# unipolar.net
KiCad netlist of a schematic drawn in EAGLE
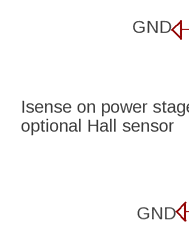
[diagram p0: schematic, sheet 1, part 1 of 2]
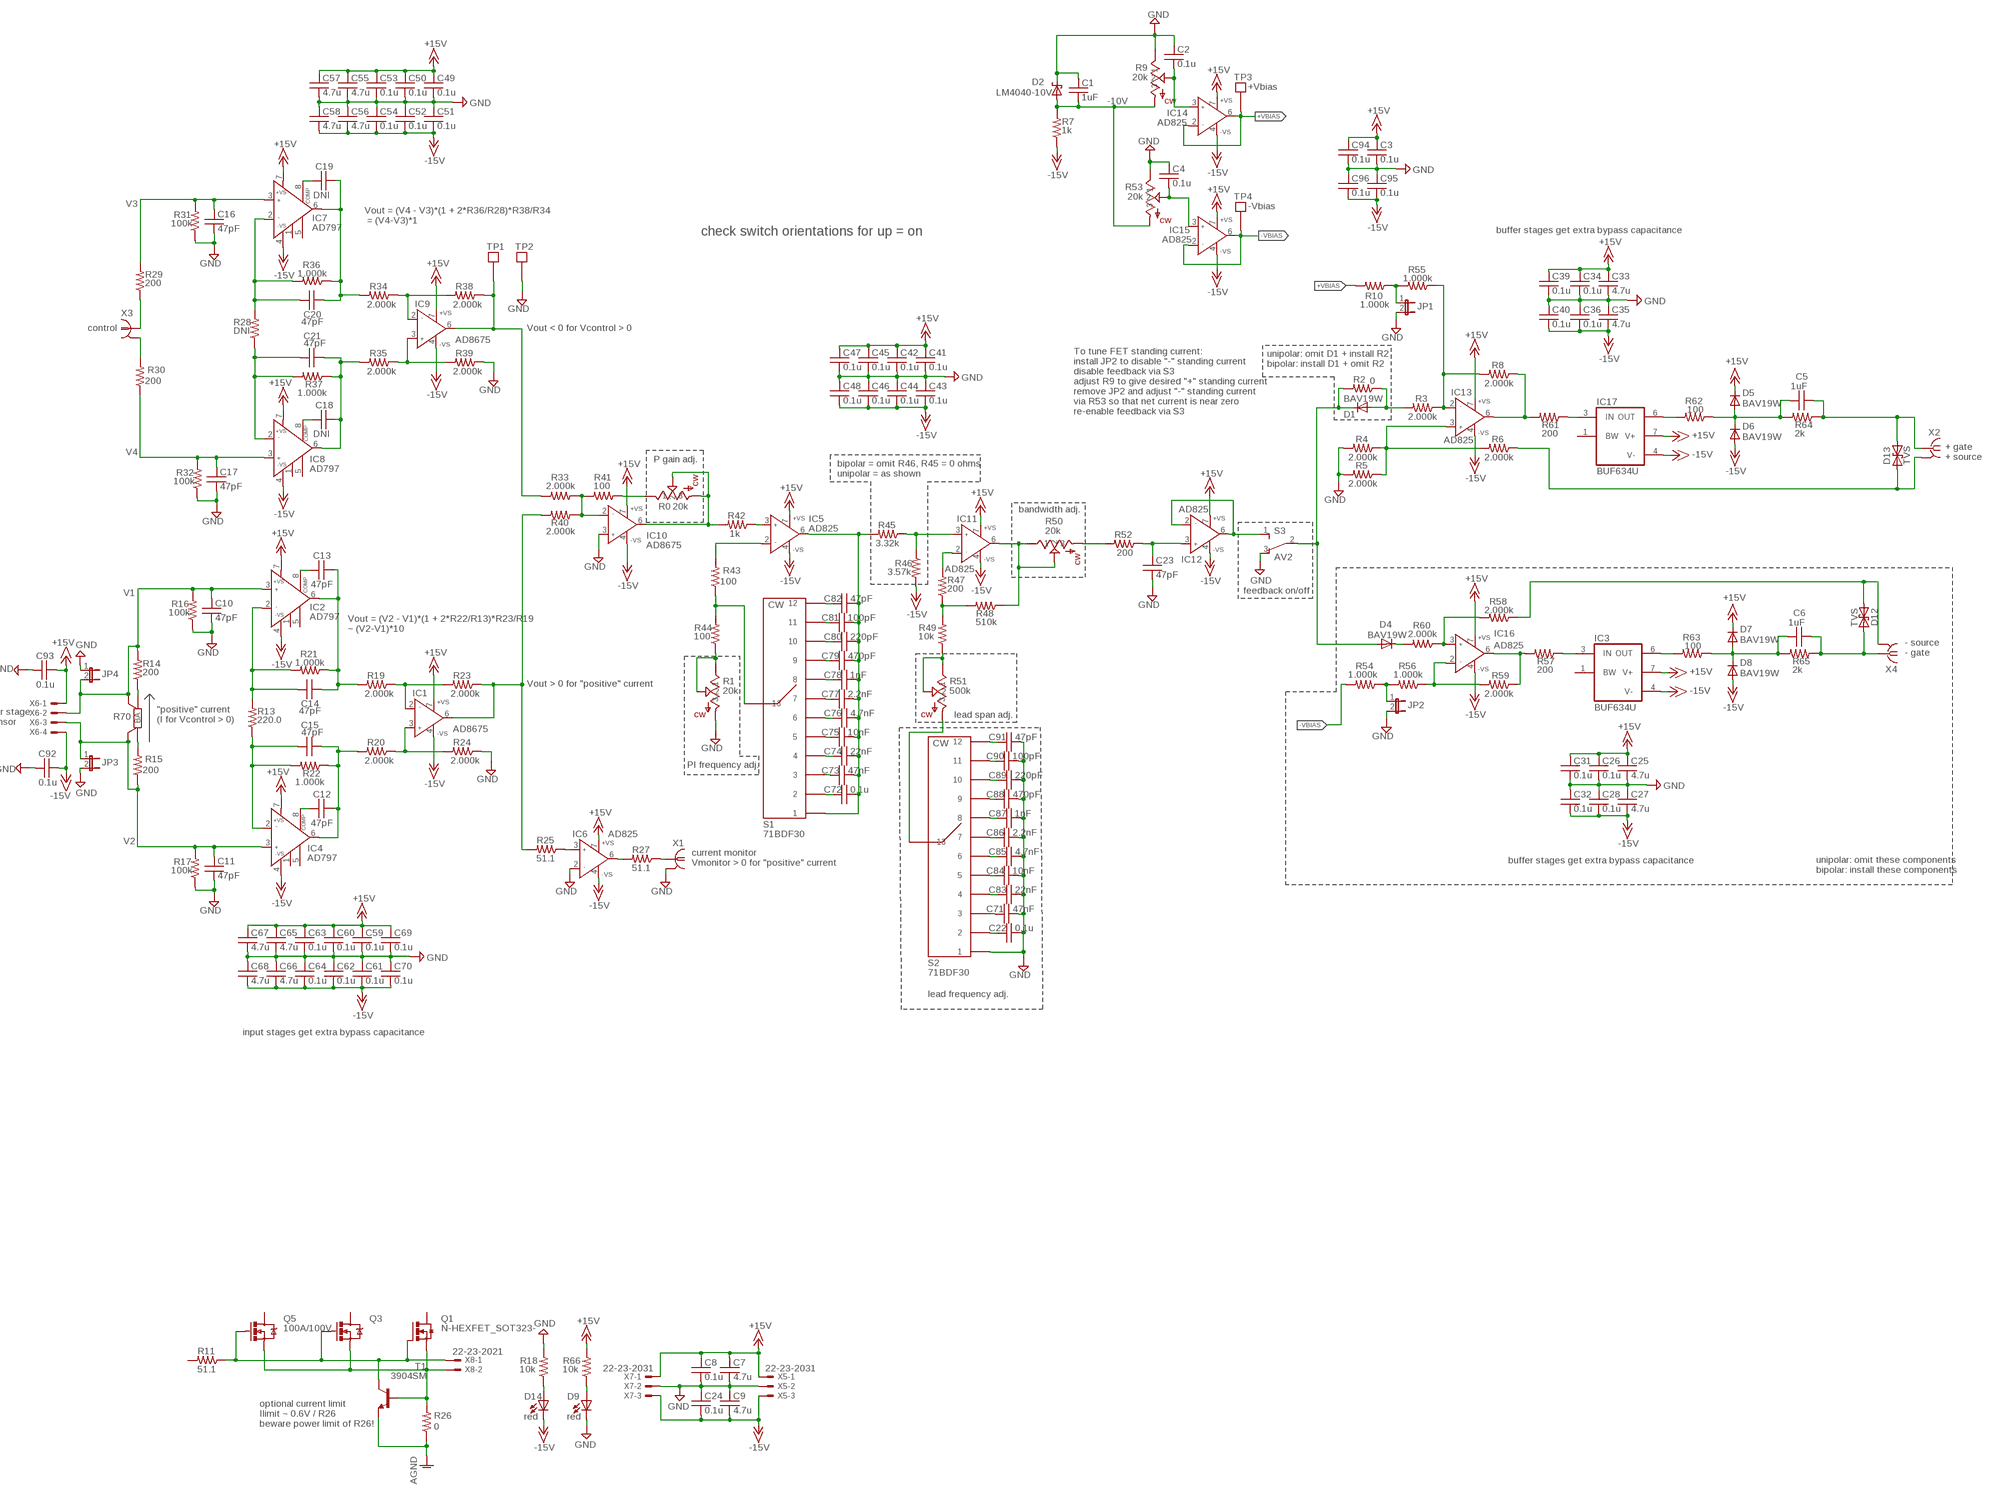
[diagram p1: schematic, sheet 1, part 2 of 2]

(export (version "E")
  (design (tool "Eeschema 10.0.6"))
  (components
    (comp (ref "C1")
      (value "1uF")
      (footprint "eagle-import:0603")
      (libsource (lib "eagle-import") (part "C0603"))
    )
    (comp (ref "C2")
      (value "0.1u")
      (footprint "eagle-import:0603")
      (libsource (lib "eagle-import") (part "C0603"))
    )
    (comp (ref "C3")
      (value "0.1u")
      (footprint "eagle-import:0603")
      (libsource (lib "eagle-import") (part "C0603"))
    )
    (comp (ref "C4")
      (value "0.1u")
      (footprint "eagle-import:0603")
      (libsource (lib "eagle-import") (part "C0603"))
    )
    (comp (ref "C5")
      (value "1uF")
      (footprint "eagle-import:0603")
      (libsource (lib "eagle-import") (part "C0603"))
    )
    (comp (ref "C6")
      (value "1uF")
      (footprint "eagle-import:0603")
      (libsource (lib "eagle-import") (part "C0603"))
    )
    (comp (ref "C7")
      (value "4.7u")
      (footprint "eagle-import:0603")
      (libsource (lib "eagle-import") (part "C0603"))
    )
    (comp (ref "C8")
      (value "0.1u")
      (footprint "eagle-import:0603")
      (libsource (lib "eagle-import") (part "C0603"))
    )
    (comp (ref "C9")
      (value "4.7u")
      (footprint "eagle-import:0603")
      (libsource (lib "eagle-import") (part "C0603"))
    )
    (comp (ref "C10")
      (value "47pF")
      (footprint "eagle-import:0603")
      (libsource (lib "eagle-import") (part "C0603"))
    )
    (comp (ref "C11")
      (value "47pF")
      (footprint "eagle-import:0603")
      (libsource (lib "eagle-import") (part "C0603"))
    )
    (comp (ref "C12")
      (value "47pF")
      (footprint "eagle-import:0603")
      (libsource (lib "eagle-import") (part "C0603"))
    )
    (comp (ref "C13")
      (value "47pF")
      (footprint "eagle-import:0603")
      (libsource (lib "eagle-import") (part "C0603"))
    )
    (comp (ref "C14")
      (value "47pF")
      (footprint "eagle-import:0603")
      (libsource (lib "eagle-import") (part "C0603"))
    )
    (comp (ref "C15")
      (value "47pF")
      (footprint "eagle-import:0603")
      (libsource (lib "eagle-import") (part "C0603"))
    )
    (comp (ref "C16")
      (value "47pF")
      (footprint "eagle-import:0603")
      (libsource (lib "eagle-import") (part "C0603"))
    )
    (comp (ref "C17")
      (value "47pF")
      (footprint "eagle-import:0603")
      (libsource (lib "eagle-import") (part "C0603"))
    )
    (comp (ref "C18")
      (value "DNI")
      (footprint "eagle-import:0603")
      (libsource (lib "eagle-import") (part "C0603"))
    )
    (comp (ref "C19")
      (value "DNI")
      (footprint "eagle-import:0603")
      (libsource (lib "eagle-import") (part "C0603"))
    )
    (comp (ref "C20")
      (value "47pF")
      (footprint "eagle-import:0603")
      (libsource (lib "eagle-import") (part "C0603"))
    )
    (comp (ref "C21")
      (value "47pF")
      (footprint "eagle-import:0603")
      (libsource (lib "eagle-import") (part "C0603"))
    )
    (comp (ref "C22")
      (value "0.1u")
      (footprint "eagle-import:0603")
      (libsource (lib "eagle-import") (part "C0603"))
    )
    (comp (ref "C23")
      (value "47pF")
      (footprint "eagle-import:0603")
      (libsource (lib "eagle-import") (part "C0603"))
    )
    (comp (ref "C24")
      (value "0.1u")
      (footprint "eagle-import:0603")
      (libsource (lib "eagle-import") (part "C0603"))
    )
    (comp (ref "C25")
      (value "4.7u")
      (footprint "eagle-import:0603")
      (libsource (lib "eagle-import") (part "C0603"))
    )
    (comp (ref "C26")
      (value "0.1u")
      (footprint "eagle-import:0603")
      (libsource (lib "eagle-import") (part "C0603"))
    )
    (comp (ref "C27")
      (value "4.7u")
      (footprint "eagle-import:0603")
      (libsource (lib "eagle-import") (part "C0603"))
    )
    (comp (ref "C28")
      (value "0.1u")
      (footprint "eagle-import:0603")
      (libsource (lib "eagle-import") (part "C0603"))
    )
    (comp (ref "C31")
      (value "0.1u")
      (footprint "eagle-import:0603")
      (libsource (lib "eagle-import") (part "C0603"))
    )
    (comp (ref "C32")
      (value "0.1u")
      (footprint "eagle-import:0603")
      (libsource (lib "eagle-import") (part "C0603"))
    )
    (comp (ref "C33")
      (value "4.7u")
      (footprint "eagle-import:0603")
      (libsource (lib "eagle-import") (part "C0603"))
    )
    (comp (ref "C34")
      (value "0.1u")
      (footprint "eagle-import:0603")
      (libsource (lib "eagle-import") (part "C0603"))
    )
    (comp (ref "C35")
      (value "4.7u")
      (footprint "eagle-import:0603")
      (libsource (lib "eagle-import") (part "C0603"))
    )
    (comp (ref "C36")
      (value "0.1u")
      (footprint "eagle-import:0603")
      (libsource (lib "eagle-import") (part "C0603"))
    )
    (comp (ref "C39")
      (value "0.1u")
      (footprint "eagle-import:0603")
      (libsource (lib "eagle-import") (part "C0603"))
    )
    (comp (ref "C40")
      (value "0.1u")
      (footprint "eagle-import:0603")
      (libsource (lib "eagle-import") (part "C0603"))
    )
    (comp (ref "C41")
      (value "0.1u")
      (footprint "eagle-import:0603")
      (libsource (lib "eagle-import") (part "C0603"))
    )
    (comp (ref "C42")
      (value "0.1u")
      (footprint "eagle-import:0603")
      (libsource (lib "eagle-import") (part "C0603"))
    )
    (comp (ref "C43")
      (value "0.1u")
      (footprint "eagle-import:0603")
      (libsource (lib "eagle-import") (part "C0603"))
    )
    (comp (ref "C44")
      (value "0.1u")
      (footprint "eagle-import:0603")
      (libsource (lib "eagle-import") (part "C0603"))
    )
    (comp (ref "C45")
      (value "0.1u")
      (footprint "eagle-import:0603")
      (libsource (lib "eagle-import") (part "C0603"))
    )
    (comp (ref "C46")
      (value "0.1u")
      (footprint "eagle-import:0603")
      (libsource (lib "eagle-import") (part "C0603"))
    )
    (comp (ref "C47")
      (value "0.1u")
      (footprint "eagle-import:0603")
      (libsource (lib "eagle-import") (part "C0603"))
    )
    (comp (ref "C48")
      (value "0.1u")
      (footprint "eagle-import:0603")
      (libsource (lib "eagle-import") (part "C0603"))
    )
    (comp (ref "C49")
      (value "0.1u")
      (footprint "eagle-import:0603")
      (libsource (lib "eagle-import") (part "C0603"))
    )
    (comp (ref "C50")
      (value "0.1u")
      (footprint "eagle-import:0603")
      (libsource (lib "eagle-import") (part "C0603"))
    )
    (comp (ref "C51")
      (value "0.1u")
      (footprint "eagle-import:0603")
      (libsource (lib "eagle-import") (part "C0603"))
    )
    (comp (ref "C52")
      (value "0.1u")
      (footprint "eagle-import:0603")
      (libsource (lib "eagle-import") (part "C0603"))
    )
    (comp (ref "C53")
      (value "0.1u")
      (footprint "eagle-import:0603")
      (libsource (lib "eagle-import") (part "C0603"))
    )
    (comp (ref "C54")
      (value "0.1u")
      (footprint "eagle-import:0603")
      (libsource (lib "eagle-import") (part "C0603"))
    )
    (comp (ref "C55")
      (value "4.7u")
      (footprint "eagle-import:0603")
      (libsource (lib "eagle-import") (part "C0603"))
    )
    (comp (ref "C56")
      (value "4.7u")
      (footprint "eagle-import:0603")
      (libsource (lib "eagle-import") (part "C0603"))
    )
    (comp (ref "C57")
      (value "4.7u")
      (footprint "eagle-import:0603")
      (libsource (lib "eagle-import") (part "C0603"))
    )
    (comp (ref "C58")
      (value "4.7u")
      (footprint "eagle-import:0603")
      (libsource (lib "eagle-import") (part "C0603"))
    )
    (comp (ref "C59")
      (value "0.1u")
      (footprint "eagle-import:0603")
      (libsource (lib "eagle-import") (part "C0603"))
    )
    (comp (ref "C60")
      (value "0.1u")
      (footprint "eagle-import:0603")
      (libsource (lib "eagle-import") (part "C0603"))
    )
    (comp (ref "C61")
      (value "0.1u")
      (footprint "eagle-import:0603")
      (libsource (lib "eagle-import") (part "C0603"))
    )
    (comp (ref "C62")
      (value "0.1u")
      (footprint "eagle-import:0603")
      (libsource (lib "eagle-import") (part "C0603"))
    )
    (comp (ref "C63")
      (value "0.1u")
      (footprint "eagle-import:0603")
      (libsource (lib "eagle-import") (part "C0603"))
    )
    (comp (ref "C64")
      (value "0.1u")
      (footprint "eagle-import:0603")
      (libsource (lib "eagle-import") (part "C0603"))
    )
    (comp (ref "C65")
      (value "4.7u")
      (footprint "eagle-import:0603")
      (libsource (lib "eagle-import") (part "C0603"))
    )
    (comp (ref "C66")
      (value "4.7u")
      (footprint "eagle-import:0603")
      (libsource (lib "eagle-import") (part "C0603"))
    )
    (comp (ref "C67")
      (value "4.7u")
      (footprint "eagle-import:0603")
      (libsource (lib "eagle-import") (part "C0603"))
    )
    (comp (ref "C68")
      (value "4.7u")
      (footprint "eagle-import:0603")
      (libsource (lib "eagle-import") (part "C0603"))
    )
    (comp (ref "C69")
      (value "0.1u")
      (footprint "eagle-import:0603")
      (libsource (lib "eagle-import") (part "C0603"))
    )
    (comp (ref "C70")
      (value "0.1u")
      (footprint "eagle-import:0603")
      (libsource (lib "eagle-import") (part "C0603"))
    )
    (comp (ref "C71")
      (value "47nF")
      (footprint "eagle-import:0603")
      (libsource (lib "eagle-import") (part "C0603"))
    )
    (comp (ref "C72")
      (value "0.1u")
      (footprint "eagle-import:0603")
      (libsource (lib "eagle-import") (part "C0603"))
    )
    (comp (ref "C73")
      (value "47nF")
      (footprint "eagle-import:0603")
      (libsource (lib "eagle-import") (part "C0603"))
    )
    (comp (ref "C74")
      (value "22nF")
      (footprint "eagle-import:0603")
      (libsource (lib "eagle-import") (part "C0603"))
    )
    (comp (ref "C75")
      (value "10nF")
      (footprint "eagle-import:0603")
      (libsource (lib "eagle-import") (part "C0603"))
    )
    (comp (ref "C76")
      (value "4.7nF")
      (footprint "eagle-import:0603")
      (libsource (lib "eagle-import") (part "C0603"))
    )
    (comp (ref "C77")
      (value "2.2nF")
      (footprint "eagle-import:0603")
      (libsource (lib "eagle-import") (part "C0603"))
    )
    (comp (ref "C78")
      (value "1nF")
      (footprint "eagle-import:0603")
      (libsource (lib "eagle-import") (part "C0603"))
    )
    (comp (ref "C79")
      (value "470pF")
      (footprint "eagle-import:0603")
      (libsource (lib "eagle-import") (part "C0603"))
    )
    (comp (ref "C80")
      (value "220pF")
      (footprint "eagle-import:0603")
      (libsource (lib "eagle-import") (part "C0603"))
    )
    (comp (ref "C81")
      (value "100pF")
      (footprint "eagle-import:0603")
      (libsource (lib "eagle-import") (part "C0603"))
    )
    (comp (ref "C82")
      (value "47pF")
      (footprint "eagle-import:0603")
      (libsource (lib "eagle-import") (part "C0603"))
    )
    (comp (ref "C83")
      (value "22nF")
      (footprint "eagle-import:0603")
      (libsource (lib "eagle-import") (part "C0603"))
    )
    (comp (ref "C84")
      (value "10nF")
      (footprint "eagle-import:0603")
      (libsource (lib "eagle-import") (part "C0603"))
    )
    (comp (ref "C85")
      (value "4.7nF")
      (footprint "eagle-import:0603")
      (libsource (lib "eagle-import") (part "C0603"))
    )
    (comp (ref "C86")
      (value "2.2nF")
      (footprint "eagle-import:0603")
      (libsource (lib "eagle-import") (part "C0603"))
    )
    (comp (ref "C87")
      (value "1nF")
      (footprint "eagle-import:0603")
      (libsource (lib "eagle-import") (part "C0603"))
    )
    (comp (ref "C88")
      (value "470pF")
      (footprint "eagle-import:0603")
      (libsource (lib "eagle-import") (part "C0603"))
    )
    (comp (ref "C89")
      (value "220pF")
      (footprint "eagle-import:0603")
      (libsource (lib "eagle-import") (part "C0603"))
    )
    (comp (ref "C90")
      (value "100pF")
      (footprint "eagle-import:0603")
      (libsource (lib "eagle-import") (part "C0603"))
    )
    (comp (ref "C91")
      (value "47pF")
      (footprint "eagle-import:0603")
      (libsource (lib "eagle-import") (part "C0603"))
    )
    (comp (ref "C92")
      (value "0.1u")
      (footprint "eagle-import:0603")
      (libsource (lib "eagle-import") (part "C0603"))
    )
    (comp (ref "C93")
      (value "0.1u")
      (footprint "eagle-import:0603")
      (libsource (lib "eagle-import") (part "C0603"))
    )
    (comp (ref "C94")
      (value "0.1u")
      (footprint "eagle-import:0603")
      (libsource (lib "eagle-import") (part "C0603"))
    )
    (comp (ref "C95")
      (value "0.1u")
      (footprint "eagle-import:0603")
      (libsource (lib "eagle-import") (part "C0603"))
    )
    (comp (ref "C96")
      (value "0.1u")
      (footprint "eagle-import:0603")
      (libsource (lib "eagle-import") (part "C0603"))
    )
    (comp (ref "D1")
      (value "BAV19W")
      (footprint "eagle-import:SOD123")
      (libsource (lib "eagle-import") (part "DIODE-SOD123"))
    )
    (comp (ref "D2")
      (value "LM4040-10V")
      (footprint "eagle-import:SOT23")
      (libsource (lib "eagle-import") (part "LM4040"))
    )
    (comp (ref "D4")
      (value "BAV19W")
      (footprint "eagle-import:SOD123")
      (libsource (lib "eagle-import") (part "DIODE-SOD123"))
    )
    (comp (ref "D5")
      (value "BAV19W")
      (footprint "eagle-import:SOD123")
      (libsource (lib "eagle-import") (part "DIODE-SOD123"))
    )
    (comp (ref "D6")
      (value "BAV19W")
      (footprint "eagle-import:SOD123")
      (libsource (lib "eagle-import") (part "DIODE-SOD123"))
    )
    (comp (ref "D7")
      (value "BAV19W")
      (footprint "eagle-import:SOD123")
      (libsource (lib "eagle-import") (part "DIODE-SOD123"))
    )
    (comp (ref "D8")
      (value "BAV19W")
      (footprint "eagle-import:SOD123")
      (libsource (lib "eagle-import") (part "DIODE-SOD123"))
    )
    (comp (ref "D9")
      (value "red")
      (footprint "eagle-import:LED0603")
      (libsource (lib "eagle-import") (part "LED0603"))
    )
    (comp (ref "D12")
      (value "TVS")
      (footprint "eagle-import:SMA-DIODE")
      (libsource (lib "eagle-import") (part "TVS"))
    )
    (comp (ref "D13")
      (value "TVS")
      (footprint "eagle-import:SMA-DIODE")
      (libsource (lib "eagle-import") (part "TVS"))
    )
    (comp (ref "D14")
      (value "red")
      (footprint "eagle-import:LED0603")
      (libsource (lib "eagle-import") (part "LED0603"))
    )
    (comp (ref "IC1")
      (value "AD8675")
      (footprint "eagle-import:SO8")
      (fields (field (name "MF") "ALTERA CORPORATION") (field (name "MPN") "AD825ARZ"))
      (libsource (lib "eagle-import") (part "AD825_BR"))
    )
    (comp (ref "IC2")
      (value "AD797")
      (footprint "eagle-import:SO8")
      (fields (field (name "MF") "ALTERA CORPORATION") (field (name "MPN") "AD797ARZ"))
      (libsource (lib "eagle-import") (part "AD797_AR"))
    )
    (comp (ref "IC3")
      (value "BUF634U")
      (footprint "eagle-import:SO08")
      (fields (field (name "MF") "TEXAS INSTRUMENTS"))
      (libsource (lib "eagle-import") (part "BUF634U"))
    )
    (comp (ref "IC4")
      (value "AD797")
      (footprint "eagle-import:SO8")
      (fields (field (name "MF") "ALTERA CORPORATION") (field (name "MPN") "AD797ARZ"))
      (libsource (lib "eagle-import") (part "AD797_BR"))
    )
    (comp (ref "IC5")
      (value "AD825")
      (footprint "eagle-import:SO08")
      (libsource (lib "eagle-import") (part "AD825_A"))
    )
    (comp (ref "IC6")
      (value "AD825")
      (footprint "eagle-import:SO08")
      (libsource (lib "eagle-import") (part "AD825_A"))
    )
    (comp (ref "IC7")
      (value "AD797")
      (footprint "eagle-import:SO8")
      (fields (field (name "MF") "ALTERA CORPORATION") (field (name "MPN") "AD797ARZ"))
      (libsource (lib "eagle-import") (part "AD797_AR"))
    )
    (comp (ref "IC8")
      (value "AD797")
      (footprint "eagle-import:SO8")
      (fields (field (name "MF") "ALTERA CORPORATION") (field (name "MPN") "AD797ARZ"))
      (libsource (lib "eagle-import") (part "AD797_BR"))
    )
    (comp (ref "IC9")
      (value "AD8675")
      (footprint "eagle-import:SO8")
      (fields (field (name "MF") "ALTERA CORPORATION") (field (name "MPN") "AD825ARZ"))
      (libsource (lib "eagle-import") (part "AD825_BR"))
    )
    (comp (ref "IC10")
      (value "AD8675")
      (footprint "eagle-import:SO8")
      (fields (field (name "MF") "ALTERA CORPORATION") (field (name "MPN") "AD825ARZ"))
      (libsource (lib "eagle-import") (part "AD825_BR"))
    )
    (comp (ref "IC11")
      (value "AD825")
      (footprint "eagle-import:SO08")
      (libsource (lib "eagle-import") (part "AD825_A"))
    )
    (comp (ref "IC12")
      (value "AD825")
      (footprint "eagle-import:SO8")
      (fields (field (name "MF") "ALTERA CORPORATION") (field (name "MPN") "AD825ARZ"))
      (libsource (lib "eagle-import") (part "AD825_BR"))
    )
    (comp (ref "IC13")
      (value "AD825")
      (footprint "eagle-import:SO8")
      (fields (field (name "MF") "ALTERA CORPORATION") (field (name "MPN") "AD825ARZ"))
      (libsource (lib "eagle-import") (part "AD825_BR"))
    )
    (comp (ref "IC14")
      (value "AD825")
      (footprint "eagle-import:SO08")
      (libsource (lib "eagle-import") (part "AD825_A"))
    )
    (comp (ref "IC15")
      (value "AD825")
      (footprint "eagle-import:SO08")
      (libsource (lib "eagle-import") (part "AD825_A"))
    )
    (comp (ref "IC16")
      (value "AD825")
      (footprint "eagle-import:SO08")
      (libsource (lib "eagle-import") (part "AD825_A"))
    )
    (comp (ref "IC17")
      (value "BUF634U")
      (footprint "eagle-import:SO08")
      (fields (field (name "MF") "TEXAS INSTRUMENTS"))
      (libsource (lib "eagle-import") (part "BUF634U"))
    )
    (comp (ref "JP1")
      (value "JP1E")
      (footprint "eagle-import:JP1")
      (libsource (lib "eagle-import") (part "JP1E"))
    )
    (comp (ref "JP2")
      (value "JP1E")
      (footprint "eagle-import:JP1")
      (libsource (lib "eagle-import") (part "JP1E"))
    )
    (comp (ref "JP3")
      (value "JP1E")
      (footprint "eagle-import:JP1")
      (libsource (lib "eagle-import") (part "JP1E"))
    )
    (comp (ref "JP4")
      (value "JP1E")
      (footprint "eagle-import:JP1")
      (libsource (lib "eagle-import") (part "JP1E"))
    )
    (comp (ref "Q1")
      (value "N-HEXFET_SOT323-")
      (footprint "eagle-import:SOT223")
      (libsource (lib "eagle-import") (part "N-HEXFET_?-SOT323"))
    )
    (comp (ref "Q3")
      (value "MOSFET-NCHANNELFDD8780")
      (footprint "eagle-import:DPAK")
      (libsource (lib "eagle-import") (part "MOSFET-NCHANNELFDD8780"))
    )
    (comp (ref "Q5")
      (value "100A/100V")
      (footprint "eagle-import:TO-263_D2PAK")
      (libsource (lib "eagle-import") (part "MOSFET-NCHANNELPSMN7R0"))
    )
    (comp (ref "R0")
      (value "20k")
      (footprint "eagle-import:3590")
      (libsource (lib "eagle-import") (part "POT"))
    )
    (comp (ref "R1")
      (value "20k")
      (footprint "eagle-import:SP19L")
      (libsource (lib "eagle-import") (part "TRIM_US-B90P"))
    )
    (comp (ref "R2")
      (value "0")
      (footprint "eagle-import:0603")
      (libsource (lib "eagle-import") (part "R0603"))
    )
    (comp (ref "R3")
      (value "2.000k")
      (footprint "eagle-import:0603")
      (libsource (lib "eagle-import") (part "R0603"))
    )
    (comp (ref "R4")
      (value "2.000k")
      (footprint "eagle-import:0603")
      (libsource (lib "eagle-import") (part "R0603"))
    )
    (comp (ref "R5")
      (value "2.000k")
      (footprint "eagle-import:0603")
      (libsource (lib "eagle-import") (part "R0603"))
    )
    (comp (ref "R6")
      (value "2.000k")
      (footprint "eagle-import:0603")
      (libsource (lib "eagle-import") (part "R0603"))
    )
    (comp (ref "R7")
      (value "1k")
      (footprint "eagle-import:0603")
      (libsource (lib "eagle-import") (part "R0603"))
    )
    (comp (ref "R8")
      (value "2.000k")
      (footprint "eagle-import:0603")
      (libsource (lib "eagle-import") (part "R0603"))
    )
    (comp (ref "R9")
      (value "20k")
      (footprint "eagle-import:SP19L")
      (libsource (lib "eagle-import") (part "TRIM_US-B90P"))
    )
    (comp (ref "R10")
      (value "1.000k")
      (footprint "eagle-import:0603")
      (libsource (lib "eagle-import") (part "R0603"))
    )
    (comp (ref "R11")
      (value "51.1")
      (footprint "eagle-import:0603")
      (libsource (lib "eagle-import") (part "R0603"))
    )
    (comp (ref "R13")
      (value "220.0")
      (footprint "eagle-import:0603")
      (libsource (lib "eagle-import") (part "R0603"))
    )
    (comp (ref "R14")
      (value "200")
      (footprint "eagle-import:0603")
      (libsource (lib "eagle-import") (part "R0603"))
    )
    (comp (ref "R15")
      (value "200")
      (footprint "eagle-import:0603")
      (libsource (lib "eagle-import") (part "R0603"))
    )
    (comp (ref "R16")
      (value "100k")
      (footprint "eagle-import:0603")
      (libsource (lib "eagle-import") (part "R0603"))
    )
    (comp (ref "R17")
      (value "100k")
      (footprint "eagle-import:0603")
      (libsource (lib "eagle-import") (part "R0603"))
    )
    (comp (ref "R18")
      (value "10k")
      (footprint "eagle-import:0603")
      (libsource (lib "eagle-import") (part "R0603"))
    )
    (comp (ref "R19")
      (value "2.000k")
      (footprint "eagle-import:0603")
      (libsource (lib "eagle-import") (part "R0603"))
    )
    (comp (ref "R20")
      (value "2.000k")
      (footprint "eagle-import:0603")
      (libsource (lib "eagle-import") (part "R0603"))
    )
    (comp (ref "R21")
      (value "1.000k")
      (footprint "eagle-import:0603")
      (libsource (lib "eagle-import") (part "R0603"))
    )
    (comp (ref "R22")
      (value "1.000k")
      (footprint "eagle-import:0603")
      (libsource (lib "eagle-import") (part "R0603"))
    )
    (comp (ref "R23")
      (value "2.000k")
      (footprint "eagle-import:0603")
      (libsource (lib "eagle-import") (part "R0603"))
    )
    (comp (ref "R24")
      (value "2.000k")
      (footprint "eagle-import:0603")
      (libsource (lib "eagle-import") (part "R0603"))
    )
    (comp (ref "R25")
      (value "51.1")
      (footprint "eagle-import:0603")
      (libsource (lib "eagle-import") (part "R0603"))
    )
    (comp (ref "R26")
      (value "0")
      (footprint "eagle-import:2512")
      (libsource (lib "eagle-import") (part "RESISTOR2512"))
    )
    (comp (ref "R27")
      (value "51.1")
      (footprint "eagle-import:0603")
      (libsource (lib "eagle-import") (part "R0603"))
    )
    (comp (ref "R28")
      (value "DNI")
      (footprint "eagle-import:0603")
      (libsource (lib "eagle-import") (part "R0603"))
    )
    (comp (ref "R29")
      (value "200")
      (footprint "eagle-import:0603")
      (libsource (lib "eagle-import") (part "R0603"))
    )
    (comp (ref "R30")
      (value "200")
      (footprint "eagle-import:0603")
      (libsource (lib "eagle-import") (part "R0603"))
    )
    (comp (ref "R31")
      (value "100k")
      (footprint "eagle-import:0603")
      (libsource (lib "eagle-import") (part "R0603"))
    )
    (comp (ref "R32")
      (value "100k")
      (footprint "eagle-import:0603")
      (libsource (lib "eagle-import") (part "R0603"))
    )
    (comp (ref "R33")
      (value "2.000k")
      (footprint "eagle-import:0603")
      (libsource (lib "eagle-import") (part "R0603"))
    )
    (comp (ref "R34")
      (value "2.000k")
      (footprint "eagle-import:0603")
      (libsource (lib "eagle-import") (part "R0603"))
    )
    (comp (ref "R35")
      (value "2.000k")
      (footprint "eagle-import:0603")
      (libsource (lib "eagle-import") (part "R0603"))
    )
    (comp (ref "R36")
      (value "1.000k")
      (footprint "eagle-import:0603")
      (libsource (lib "eagle-import") (part "R0603"))
    )
    (comp (ref "R37")
      (value "1.000k")
      (footprint "eagle-import:0603")
      (libsource (lib "eagle-import") (part "R0603"))
    )
    (comp (ref "R38")
      (value "2.000k")
      (footprint "eagle-import:0603")
      (libsource (lib "eagle-import") (part "R0603"))
    )
    (comp (ref "R39")
      (value "2.000k")
      (footprint "eagle-import:0603")
      (libsource (lib "eagle-import") (part "R0603"))
    )
    (comp (ref "R40")
      (value "2.000k")
      (footprint "eagle-import:0603")
      (libsource (lib "eagle-import") (part "R0603"))
    )
    (comp (ref "R41")
      (value "100")
      (footprint "eagle-import:0603")
      (libsource (lib "eagle-import") (part "R0603"))
    )
    (comp (ref "R42")
      (value "1k")
      (footprint "eagle-import:0603")
      (libsource (lib "eagle-import") (part "R0603"))
    )
    (comp (ref "R43")
      (value "100")
      (footprint "eagle-import:0603")
      (libsource (lib "eagle-import") (part "R0603"))
    )
    (comp (ref "R44")
      (value "100")
      (footprint "eagle-import:0603")
      (libsource (lib "eagle-import") (part "R0603"))
    )
    (comp (ref "R45")
      (value "3.32k")
      (footprint "eagle-import:0603")
      (libsource (lib "eagle-import") (part "R0603"))
    )
    (comp (ref "R46")
      (value "3.57k")
      (footprint "eagle-import:0603")
      (libsource (lib "eagle-import") (part "R0603"))
    )
    (comp (ref "R47")
      (value "200")
      (footprint "eagle-import:0603")
      (libsource (lib "eagle-import") (part "R0603"))
    )
    (comp (ref "R48")
      (value "510k")
      (footprint "eagle-import:0603")
      (libsource (lib "eagle-import") (part "R0603"))
    )
    (comp (ref "R49")
      (value "10k")
      (footprint "eagle-import:0603")
      (libsource (lib "eagle-import") (part "R0603"))
    )
    (comp (ref "R50")
      (value "20k")
      (footprint "eagle-import:SP19L")
      (libsource (lib "eagle-import") (part "TRIM_US-B90P"))
    )
    (comp (ref "R51")
      (value "500k")
      (footprint "eagle-import:SP19L")
      (libsource (lib "eagle-import") (part "TRIM_US-B90P"))
    )
    (comp (ref "R52")
      (value "200")
      (footprint "eagle-import:0603")
      (libsource (lib "eagle-import") (part "R0603"))
    )
    (comp (ref "R53")
      (value "20k")
      (footprint "eagle-import:SP19L")
      (libsource (lib "eagle-import") (part "TRIM_US-B90P"))
    )
    (comp (ref "R54")
      (value "1.000k")
      (footprint "eagle-import:0603")
      (libsource (lib "eagle-import") (part "R0603"))
    )
    (comp (ref "R55")
      (value "1.000k")
      (footprint "eagle-import:0603")
      (libsource (lib "eagle-import") (part "R0603"))
    )
    (comp (ref "R56")
      (value "1.000k")
      (footprint "eagle-import:0603")
      (libsource (lib "eagle-import") (part "R0603"))
    )
    (comp (ref "R57")
      (value "200")
      (footprint "eagle-import:0603")
      (libsource (lib "eagle-import") (part "R0603"))
    )
    (comp (ref "R58")
      (value "2.000k")
      (footprint "eagle-import:0603")
      (libsource (lib "eagle-import") (part "R0603"))
    )
    (comp (ref "R59")
      (value "2.000k")
      (footprint "eagle-import:0603")
      (libsource (lib "eagle-import") (part "R0603"))
    )
    (comp (ref "R60")
      (value "2.000k")
      (footprint "eagle-import:0603")
      (libsource (lib "eagle-import") (part "R0603"))
    )
    (comp (ref "R61")
      (value "200")
      (footprint "eagle-import:0603")
      (libsource (lib "eagle-import") (part "R0603"))
    )
    (comp (ref "R62")
      (value "100")
      (footprint "eagle-import:0603")
      (libsource (lib "eagle-import") (part "R0603"))
    )
    (comp (ref "R63")
      (value "100")
      (footprint "eagle-import:0603")
      (libsource (lib "eagle-import") (part "R0603"))
    )
    (comp (ref "R64")
      (value "2k")
      (footprint "eagle-import:0603")
      (libsource (lib "eagle-import") (part "R0603"))
    )
    (comp (ref "R65")
      (value "2k")
      (footprint "eagle-import:0603")
      (libsource (lib "eagle-import") (part "R0603"))
    )
    (comp (ref "R66")
      (value "10k")
      (footprint "eagle-import:0603")
      (libsource (lib "eagle-import") (part "R0603"))
    )
    (comp (ref "R70")
      (value "RSENSE")
      (footprint "eagle-import:22-23-2041")
      (libsource (lib "eagle-import") (part "RSENSE"))
    )
    (comp (ref "S1")
      (value "71BDF30")
      (footprint "eagle-import:71BDF")
      (libsource (lib "eagle-import") (part "71BDF30"))
    )
    (comp (ref "S2")
      (value "71BDF30")
      (footprint "eagle-import:71BDF")
      (libsource (lib "eagle-import") (part "71BDF30"))
    )
    (comp (ref "S3")
      (value "AV2")
      (footprint "eagle-import:SPDT-AV2")
      (libsource (lib "eagle-import") (part "SPDT"))
    )
    (comp (ref "T1")
      (value "3904SM")
      (footprint "eagle-import:SOT23")
      (libsource (lib "eagle-import") (part "3904SM"))
    )
    (comp (ref "TP1")
      (value "TESTPOINT")
      (footprint "eagle-import:TESTPOINT")
      (libsource (lib "eagle-import") (part "TESTPOINT"))
    )
    (comp (ref "TP2")
      (value "TESTPOINT")
      (footprint "eagle-import:TESTPOINT")
      (libsource (lib "eagle-import") (part "TESTPOINT"))
    )
    (comp (ref "TP3")
      (value "TESTPOINT")
      (footprint "eagle-import:TESTPOINT")
      (libsource (lib "eagle-import") (part "TESTPOINT"))
    )
    (comp (ref "TP4")
      (value "TESTPOINT")
      (footprint "eagle-import:TESTPOINT")
      (libsource (lib "eagle-import") (part "TESTPOINT"))
    )
    (comp (ref "X1")
      (value "1-227161-0")
      (footprint "eagle-import:AMP_227161")
      (fields (field (name "MF") "TYCO ELECTRONICS") (field (name "MPN") "1-227161"))
      (libsource (lib "eagle-import") (part "?2271611--0"))
    )
    (comp (ref "X2")
      (value "BU-SMA-H")
      (footprint "eagle-import:BU-SMA-H")
      (libsource (lib "eagle-import") (part "BU-SMA-H"))
    )
    (comp (ref "X3")
      (value "1-227161-0")
      (footprint "eagle-import:AMP_227161")
      (fields (field (name "MF") "TYCO ELECTRONICS") (field (name "MPN") "1-227161"))
      (libsource (lib "eagle-import") (part "?2271611--0"))
    )
    (comp (ref "X4")
      (value "BU-SMA-H")
      (footprint "eagle-import:BU-SMA-H")
      (libsource (lib "eagle-import") (part "BU-SMA-H"))
    )
    (comp (ref "X5")
      (value "22-23-2031")
      (footprint "eagle-import:22-23-2031")
      (fields (field (name "MF") "MOLEX"))
      (libsource (lib "eagle-import") (part "22-23-2031"))
    )
    (comp (ref "X6")
      (value "22-23-2041")
      (footprint "eagle-import:22-23-2041")
      (fields (field (name "MF") "MOLEX"))
      (libsource (lib "eagle-import") (part "22-23-2041"))
    )
    (comp (ref "X7")
      (value "22-23-2031")
      (footprint "eagle-import:22-23-2031")
      (fields (field (name "MF") "MOLEX"))
      (libsource (lib "eagle-import") (part "22-23-2031"))
    )
    (comp (ref "X8")
      (value "22-23-2021")
      (footprint "eagle-import:22-23-2021")
      (fields (field (name "MF") "MOLEX"))
      (libsource (lib "eagle-import") (part "22-23-2021"))
    )
  )
  (nets
    (net (code "1") (name "+15V") (class "Default")
      (node (ref "C25") (pin "1") (pinfunction "1_1") (pintype "passive"))
      (node (ref "C26") (pin "1") (pinfunction "1_1") (pintype "passive"))
      (node (ref "C3") (pin "1") (pinfunction "1_1") (pintype "passive"))
      (node (ref "C31") (pin "1") (pinfunction "1_1") (pintype "passive"))
      (node (ref "C33") (pin "1") (pinfunction "1_1") (pintype "passive"))
      (node (ref "C34") (pin "1") (pinfunction "1_1") (pintype "passive"))
      (node (ref "C39") (pin "1") (pinfunction "1_1") (pintype "passive"))
      (node (ref "C41") (pin "1") (pinfunction "1_1") (pintype "passive"))
      (node (ref "C42") (pin "1") (pinfunction "1_1") (pintype "passive"))
      (node (ref "C45") (pin "1") (pinfunction "1_1") (pintype "passive"))
      (node (ref "C47") (pin "1") (pinfunction "1_1") (pintype "passive"))
      (node (ref "C49") (pin "1") (pinfunction "1_1") (pintype "passive"))
      (node (ref "C50") (pin "1") (pinfunction "1_1") (pintype "passive"))
      (node (ref "C53") (pin "1") (pinfunction "1_1") (pintype "passive"))
      (node (ref "C55") (pin "1") (pinfunction "1_1") (pintype "passive"))
      (node (ref "C57") (pin "1") (pinfunction "1_1") (pintype "passive"))
      (node (ref "C59") (pin "1") (pinfunction "1_1") (pintype "passive"))
      (node (ref "C60") (pin "1") (pinfunction "1_1") (pintype "passive"))
      (node (ref "C63") (pin "1") (pinfunction "1_1") (pintype "passive"))
      (node (ref "C65") (pin "1") (pinfunction "1_1") (pintype "passive"))
      (node (ref "C67") (pin "1") (pinfunction "1_1") (pintype "passive"))
      (node (ref "C69") (pin "1") (pinfunction "1_1") (pintype "passive"))
      (node (ref "C7") (pin "1") (pinfunction "1_1") (pintype "passive"))
      (node (ref "C8") (pin "1") (pinfunction "1_1") (pintype "passive"))
      (node (ref "C93") (pin "2") (pinfunction "2_2") (pintype "passive"))
      (node (ref "C94") (pin "1") (pinfunction "1_1") (pintype "passive"))
      (node (ref "D5") (pin "C") (pinfunction "C_C") (pintype "passive"))
      (node (ref "D7") (pin "C") (pinfunction "C_C") (pintype "passive"))
      (node (ref "IC1") (pin "7") (pinfunction "+VS_7") (pintype "input"))
      (node (ref "IC10") (pin "7") (pinfunction "+VS_7") (pintype "input"))
      (node (ref "IC11") (pin "7") (pinfunction "+VS_7") (pintype "input"))
      (node (ref "IC12") (pin "7") (pinfunction "+VS_7") (pintype "input"))
      (node (ref "IC13") (pin "7") (pinfunction "+VS_7") (pintype "input"))
      (node (ref "IC14") (pin "7") (pinfunction "+VS_7") (pintype "input"))
      (node (ref "IC15") (pin "7") (pinfunction "+VS_7") (pintype "input"))
      (node (ref "IC16") (pin "7") (pinfunction "+VS_7") (pintype "input"))
      (node (ref "IC17") (pin "7") (pinfunction "V+_7") (pintype "power_in"))
      (node (ref "IC2") (pin "7") (pinfunction "+VS_7") (pintype "input"))
      (node (ref "IC3") (pin "7") (pinfunction "V+_7") (pintype "power_in"))
      (node (ref "IC4") (pin "7") (pinfunction "+VS_7") (pintype "input"))
      (node (ref "IC5") (pin "7") (pinfunction "+VS_7") (pintype "input"))
      (node (ref "IC6") (pin "7") (pinfunction "+VS_7") (pintype "input"))
      (node (ref "IC7") (pin "7") (pinfunction "+VS_7") (pintype "input"))
      (node (ref "IC8") (pin "7") (pinfunction "+VS_7") (pintype "input"))
      (node (ref "IC9") (pin "7") (pinfunction "+VS_7") (pintype "input"))
      (node (ref "R66") (pin "2") (pinfunction "2_2") (pintype "passive"))
      (node (ref "X5") (pin "1") (pinfunction "S_1") (pintype "passive"))
      (node (ref "X6") (pin "1") (pinfunction "S_1") (pintype "passive"))
      (node (ref "X7") (pin "1") (pinfunction "S_1") (pintype "passive"))
    )
    (net (code "2") (name "+VBIAS") (class "Default")
      (node (ref "IC14") (pin "2") (pinfunction "IN-_2") (pintype "input"))
      (node (ref "IC14") (pin "6") (pinfunction "OUT_6") (pintype "output"))
      (node (ref "R10") (pin "2") (pinfunction "2_2") (pintype "passive"))
      (node (ref "TP3") (pin "P$1") (pinfunction "P$1_P$1") (pintype "bidirectional"))
    )
    (net (code "3") (name "-15V") (class "Default")
      (node (ref "C24") (pin "2") (pinfunction "2_2") (pintype "passive"))
      (node (ref "C27") (pin "2") (pinfunction "2_2") (pintype "passive"))
      (node (ref "C28") (pin "2") (pinfunction "2_2") (pintype "passive"))
      (node (ref "C32") (pin "2") (pinfunction "2_2") (pintype "passive"))
      (node (ref "C35") (pin "2") (pinfunction "2_2") (pintype "passive"))
      (node (ref "C36") (pin "2") (pinfunction "2_2") (pintype "passive"))
      (node (ref "C40") (pin "2") (pinfunction "2_2") (pintype "passive"))
      (node (ref "C43") (pin "2") (pinfunction "2_2") (pintype "passive"))
      (node (ref "C44") (pin "2") (pinfunction "2_2") (pintype "passive"))
      (node (ref "C46") (pin "2") (pinfunction "2_2") (pintype "passive"))
      (node (ref "C48") (pin "2") (pinfunction "2_2") (pintype "passive"))
      (node (ref "C51") (pin "2") (pinfunction "2_2") (pintype "passive"))
      (node (ref "C52") (pin "2") (pinfunction "2_2") (pintype "passive"))
      (node (ref "C54") (pin "2") (pinfunction "2_2") (pintype "passive"))
      (node (ref "C56") (pin "2") (pinfunction "2_2") (pintype "passive"))
      (node (ref "C58") (pin "2") (pinfunction "2_2") (pintype "passive"))
      (node (ref "C61") (pin "2") (pinfunction "2_2") (pintype "passive"))
      (node (ref "C62") (pin "2") (pinfunction "2_2") (pintype "passive"))
      (node (ref "C64") (pin "2") (pinfunction "2_2") (pintype "passive"))
      (node (ref "C66") (pin "2") (pinfunction "2_2") (pintype "passive"))
      (node (ref "C68") (pin "2") (pinfunction "2_2") (pintype "passive"))
      (node (ref "C70") (pin "2") (pinfunction "2_2") (pintype "passive"))
      (node (ref "C9") (pin "2") (pinfunction "2_2") (pintype "passive"))
      (node (ref "C92") (pin "2") (pinfunction "2_2") (pintype "passive"))
      (node (ref "C95") (pin "2") (pinfunction "2_2") (pintype "passive"))
      (node (ref "C96") (pin "2") (pinfunction "2_2") (pintype "passive"))
      (node (ref "D14") (pin "C") (pinfunction "C_C") (pintype "passive"))
      (node (ref "D6") (pin "A") (pinfunction "A_A") (pintype "passive"))
      (node (ref "D8") (pin "A") (pinfunction "A_A") (pintype "passive"))
      (node (ref "IC1") (pin "4") (pinfunction "-VS_4") (pintype "input"))
      (node (ref "IC10") (pin "4") (pinfunction "-VS_4") (pintype "input"))
      (node (ref "IC11") (pin "4") (pinfunction "-VS_4") (pintype "input"))
      (node (ref "IC12") (pin "4") (pinfunction "-VS_4") (pintype "input"))
      (node (ref "IC13") (pin "4") (pinfunction "-VS_4") (pintype "input"))
      (node (ref "IC14") (pin "4") (pinfunction "-VS_4") (pintype "input"))
      (node (ref "IC15") (pin "4") (pinfunction "-VS_4") (pintype "input"))
      (node (ref "IC16") (pin "4") (pinfunction "-VS_4") (pintype "input"))
      (node (ref "IC17") (pin "4") (pinfunction "V-_4") (pintype "power_in"))
      (node (ref "IC2") (pin "4") (pinfunction "-VS_4") (pintype "input"))
      (node (ref "IC3") (pin "4") (pinfunction "V-_4") (pintype "power_in"))
      (node (ref "IC4") (pin "4") (pinfunction "-VS_4") (pintype "input"))
      (node (ref "IC5") (pin "4") (pinfunction "-VS_4") (pintype "input"))
      (node (ref "IC6") (pin "4") (pinfunction "-VS_4") (pintype "input"))
      (node (ref "IC7") (pin "4") (pinfunction "-VS_4") (pintype "input"))
      (node (ref "IC8") (pin "4") (pinfunction "-VS_4") (pintype "input"))
      (node (ref "IC9") (pin "4") (pinfunction "-VS_4") (pintype "input"))
      (node (ref "R46") (pin "2") (pinfunction "2_2") (pintype "passive"))
      (node (ref "R7") (pin "1") (pinfunction "1_1") (pintype "passive"))
      (node (ref "X5") (pin "3") (pinfunction "S_3") (pintype "passive"))
      (node (ref "X6") (pin "4") (pinfunction "S_4") (pintype "passive"))
      (node (ref "X7") (pin "3") (pinfunction "S_3") (pintype "passive"))
    )
    (net (code "4") (name "-VBIAS") (class "Default")
      (node (ref "IC15") (pin "2") (pinfunction "IN-_2") (pintype "input"))
      (node (ref "IC15") (pin "6") (pinfunction "OUT_6") (pintype "output"))
      (node (ref "R54") (pin "2") (pinfunction "2_2") (pintype "passive"))
      (node (ref "TP4") (pin "P$1") (pinfunction "P$1_P$1") (pintype "bidirectional"))
    )
    (net (code "5") (name "AGND") (class "Default")
      (node (ref "R26") (pin "1") (pinfunction "1_1") (pintype "passive"))
      (node (ref "T1") (pin "2") (pinfunction "E_2") (pintype "passive"))
    )
    (net (code "6") (name "GND") (class "Default")
      (node (ref "C1") (pin "1") (pinfunction "1_1") (pintype "passive"))
      (node (ref "C10") (pin "2") (pinfunction "2_2") (pintype "passive"))
      (node (ref "C11") (pin "2") (pinfunction "2_2") (pintype "passive"))
      (node (ref "C16") (pin "2") (pinfunction "2_2") (pintype "passive"))
      (node (ref "C17") (pin "2") (pinfunction "2_2") (pintype "passive"))
      (node (ref "C2") (pin "1") (pinfunction "1_1") (pintype "passive"))
      (node (ref "C22") (pin "2") (pinfunction "2_2") (pintype "passive"))
      (node (ref "C23") (pin "2") (pinfunction "2_2") (pintype "passive"))
      (node (ref "C24") (pin "1") (pinfunction "1_1") (pintype "passive"))
      (node (ref "C25") (pin "2") (pinfunction "2_2") (pintype "passive"))
      (node (ref "C26") (pin "2") (pinfunction "2_2") (pintype "passive"))
      (node (ref "C27") (pin "1") (pinfunction "1_1") (pintype "passive"))
      (node (ref "C28") (pin "1") (pinfunction "1_1") (pintype "passive"))
      (node (ref "C3") (pin "2") (pinfunction "2_2") (pintype "passive"))
      (node (ref "C31") (pin "2") (pinfunction "2_2") (pintype "passive"))
      (node (ref "C32") (pin "1") (pinfunction "1_1") (pintype "passive"))
      (node (ref "C33") (pin "2") (pinfunction "2_2") (pintype "passive"))
      (node (ref "C34") (pin "2") (pinfunction "2_2") (pintype "passive"))
      (node (ref "C35") (pin "1") (pinfunction "1_1") (pintype "passive"))
      (node (ref "C36") (pin "1") (pinfunction "1_1") (pintype "passive"))
      (node (ref "C39") (pin "2") (pinfunction "2_2") (pintype "passive"))
      (node (ref "C4") (pin "1") (pinfunction "1_1") (pintype "passive"))
      (node (ref "C40") (pin "1") (pinfunction "1_1") (pintype "passive"))
      (node (ref "C41") (pin "2") (pinfunction "2_2") (pintype "passive"))
      (node (ref "C42") (pin "2") (pinfunction "2_2") (pintype "passive"))
      (node (ref "C43") (pin "1") (pinfunction "1_1") (pintype "passive"))
      (node (ref "C44") (pin "1") (pinfunction "1_1") (pintype "passive"))
      (node (ref "C45") (pin "2") (pinfunction "2_2") (pintype "passive"))
      (node (ref "C46") (pin "1") (pinfunction "1_1") (pintype "passive"))
      (node (ref "C47") (pin "2") (pinfunction "2_2") (pintype "passive"))
      (node (ref "C48") (pin "1") (pinfunction "1_1") (pintype "passive"))
      (node (ref "C49") (pin "2") (pinfunction "2_2") (pintype "passive"))
      (node (ref "C50") (pin "2") (pinfunction "2_2") (pintype "passive"))
      (node (ref "C51") (pin "1") (pinfunction "1_1") (pintype "passive"))
      (node (ref "C52") (pin "1") (pinfunction "1_1") (pintype "passive"))
      (node (ref "C53") (pin "2") (pinfunction "2_2") (pintype "passive"))
      (node (ref "C54") (pin "1") (pinfunction "1_1") (pintype "passive"))
      (node (ref "C55") (pin "2") (pinfunction "2_2") (pintype "passive"))
      (node (ref "C56") (pin "1") (pinfunction "1_1") (pintype "passive"))
      (node (ref "C57") (pin "2") (pinfunction "2_2") (pintype "passive"))
      (node (ref "C58") (pin "1") (pinfunction "1_1") (pintype "passive"))
      (node (ref "C59") (pin "2") (pinfunction "2_2") (pintype "passive"))
      (node (ref "C60") (pin "2") (pinfunction "2_2") (pintype "passive"))
      (node (ref "C61") (pin "1") (pinfunction "1_1") (pintype "passive"))
      (node (ref "C62") (pin "1") (pinfunction "1_1") (pintype "passive"))
      (node (ref "C63") (pin "2") (pinfunction "2_2") (pintype "passive"))
      (node (ref "C64") (pin "1") (pinfunction "1_1") (pintype "passive"))
      (node (ref "C65") (pin "2") (pinfunction "2_2") (pintype "passive"))
      (node (ref "C66") (pin "1") (pinfunction "1_1") (pintype "passive"))
      (node (ref "C67") (pin "2") (pinfunction "2_2") (pintype "passive"))
      (node (ref "C68") (pin "1") (pinfunction "1_1") (pintype "passive"))
      (node (ref "C69") (pin "2") (pinfunction "2_2") (pintype "passive"))
      (node (ref "C7") (pin "2") (pinfunction "2_2") (pintype "passive"))
      (node (ref "C70") (pin "1") (pinfunction "1_1") (pintype "passive"))
      (node (ref "C71") (pin "2") (pinfunction "2_2") (pintype "passive"))
      (node (ref "C8") (pin "2") (pinfunction "2_2") (pintype "passive"))
      (node (ref "C83") (pin "2") (pinfunction "2_2") (pintype "passive"))
      (node (ref "C84") (pin "2") (pinfunction "2_2") (pintype "passive"))
      (node (ref "C85") (pin "2") (pinfunction "2_2") (pintype "passive"))
      (node (ref "C86") (pin "2") (pinfunction "2_2") (pintype "passive"))
      (node (ref "C87") (pin "2") (pinfunction "2_2") (pintype "passive"))
      (node (ref "C88") (pin "2") (pinfunction "2_2") (pintype "passive"))
      (node (ref "C89") (pin "2") (pinfunction "2_2") (pintype "passive"))
      (node (ref "C9") (pin "1") (pinfunction "1_1") (pintype "passive"))
      (node (ref "C90") (pin "2") (pinfunction "2_2") (pintype "passive"))
      (node (ref "C91") (pin "2") (pinfunction "2_2") (pintype "passive"))
      (node (ref "C92") (pin "1") (pinfunction "1_1") (pintype "passive"))
      (node (ref "C93") (pin "1") (pinfunction "1_1") (pintype "passive"))
      (node (ref "C94") (pin "2") (pinfunction "2_2") (pintype "passive"))
      (node (ref "C95") (pin "1") (pinfunction "1_1") (pintype "passive"))
      (node (ref "C96") (pin "1") (pinfunction "1_1") (pintype "passive"))
      (node (ref "D2") (pin "1") (pinfunction "C_1") (pintype "passive"))
      (node (ref "D9") (pin "C") (pinfunction "C_C") (pintype "passive"))
      (node (ref "IC10") (pin "3") (pinfunction "IN+_3") (pintype "input"))
      (node (ref "IC6") (pin "2") (pinfunction "IN-_2") (pintype "input"))
      (node (ref "JP1") (pin "2") (pinfunction "2_2") (pintype "passive"))
      (node (ref "JP2") (pin "2") (pinfunction "2_2") (pintype "passive"))
      (node (ref "JP3") (pin "2") (pinfunction "2_2") (pintype "passive"))
      (node (ref "JP4") (pin "1") (pinfunction "1_1") (pintype "passive"))
      (node (ref "R1") (pin "E") (pinfunction "3_E") (pintype "passive"))
      (node (ref "R16") (pin "1") (pinfunction "1_1") (pintype "passive"))
      (node (ref "R17") (pin "1") (pinfunction "1_1") (pintype "passive"))
      (node (ref "R18") (pin "2") (pinfunction "2_2") (pintype "passive"))
      (node (ref "R24") (pin "1") (pinfunction "1_1") (pintype "passive"))
      (node (ref "R31") (pin "1") (pinfunction "1_1") (pintype "passive"))
      (node (ref "R32") (pin "1") (pinfunction "1_1") (pintype "passive"))
      (node (ref "R39") (pin "1") (pinfunction "1_1") (pintype "passive"))
      (node (ref "R4") (pin "2") (pinfunction "2_2") (pintype "passive"))
      (node (ref "R5") (pin "2") (pinfunction "2_2") (pintype "passive"))
      (node (ref "R53") (pin "A") (pinfunction "1_A") (pintype "passive"))
      (node (ref "R9") (pin "A") (pinfunction "1_A") (pintype "passive"))
      (node (ref "S2") (pin "1") (pinfunction "1_1") (pintype "bidirectional"))
      (node (ref "S3") (pin "3") (pinfunction "3_3") (pintype "passive"))
      (node (ref "TP2") (pin "P$1") (pinfunction "P$1_P$1") (pintype "bidirectional"))
      (node (ref "X1") (pin "2") (pinfunction "2_2") (pintype "passive"))
      (node (ref "X5") (pin "2") (pinfunction "S_2") (pintype "passive"))
      (node (ref "X7") (pin "2") (pinfunction "S_2") (pintype "passive"))
    )
    (net (code "7") (name "Net-(C5-Pad1)") (class "Default")
      (node (ref "C5") (pin "1") (pinfunction "1_1") (pintype "passive"))
      (node (ref "D5") (pin "A") (pinfunction "A_A") (pintype "passive"))
      (node (ref "D6") (pin "C") (pinfunction "C_C") (pintype "passive"))
      (node (ref "R62") (pin "1") (pinfunction "1_1") (pintype "passive"))
      (node (ref "R64") (pin "2") (pinfunction "2_2") (pintype "passive"))
    )
    (net (code "8") (name "Net-(C6-Pad1)") (class "Default")
      (node (ref "C6") (pin "1") (pinfunction "1_1") (pintype "passive"))
      (node (ref "D7") (pin "A") (pinfunction "A_A") (pintype "passive"))
      (node (ref "D8") (pin "C") (pinfunction "C_C") (pintype "passive"))
      (node (ref "R63") (pin "1") (pinfunction "1_1") (pintype "passive"))
      (node (ref "R65") (pin "2") (pinfunction "2_2") (pintype "passive"))
    )
    (net (code "9") (name "Net-(C22-Pad1)") (class "Default")
      (node (ref "C22") (pin "1") (pinfunction "1_1") (pintype "passive"))
      (node (ref "S2") (pin "2") (pinfunction "2_2") (pintype "bidirectional"))
    )
    (net (code "10") (name "Net-(C71-Pad1)") (class "Default")
      (node (ref "C71") (pin "1") (pinfunction "1_1") (pintype "passive"))
      (node (ref "S2") (pin "3") (pinfunction "3_3") (pintype "bidirectional"))
    )
    (net (code "11") (name "Net-(C72-Pad1)") (class "Default")
      (node (ref "C72") (pin "1") (pinfunction "1_1") (pintype "passive"))
      (node (ref "S1") (pin "2") (pinfunction "2_2") (pintype "bidirectional"))
    )
    (net (code "12") (name "Net-(C73-Pad1)") (class "Default")
      (node (ref "C73") (pin "1") (pinfunction "1_1") (pintype "passive"))
      (node (ref "S1") (pin "3") (pinfunction "3_3") (pintype "bidirectional"))
    )
    (net (code "13") (name "Net-(C74-Pad1)") (class "Default")
      (node (ref "C74") (pin "1") (pinfunction "1_1") (pintype "passive"))
      (node (ref "S1") (pin "4") (pinfunction "4_4") (pintype "bidirectional"))
    )
    (net (code "14") (name "Net-(C75-Pad1)") (class "Default")
      (node (ref "C75") (pin "1") (pinfunction "1_1") (pintype "passive"))
      (node (ref "S1") (pin "5") (pinfunction "5_5") (pintype "bidirectional"))
    )
    (net (code "15") (name "Net-(C76-Pad1)") (class "Default")
      (node (ref "C76") (pin "1") (pinfunction "1_1") (pintype "passive"))
      (node (ref "S1") (pin "6") (pinfunction "6_6") (pintype "bidirectional"))
    )
    (net (code "16") (name "Net-(C77-Pad1)") (class "Default")
      (node (ref "C77") (pin "1") (pinfunction "1_1") (pintype "passive"))
      (node (ref "S1") (pin "7") (pinfunction "7_7") (pintype "bidirectional"))
    )
    (net (code "17") (name "Net-(C78-Pad1)") (class "Default")
      (node (ref "C78") (pin "1") (pinfunction "1_1") (pintype "passive"))
      (node (ref "S1") (pin "8") (pinfunction "8_8") (pintype "bidirectional"))
    )
    (net (code "18") (name "Net-(C79-Pad1)") (class "Default")
      (node (ref "C79") (pin "1") (pinfunction "1_1") (pintype "passive"))
      (node (ref "S1") (pin "9") (pinfunction "9_9") (pintype "bidirectional"))
    )
    (net (code "19") (name "Net-(C80-Pad1)") (class "Default")
      (node (ref "C80") (pin "1") (pinfunction "1_1") (pintype "passive"))
      (node (ref "S1") (pin "10") (pinfunction "10_10") (pintype "bidirectional"))
    )
    (net (code "20") (name "Net-(C81-Pad1)") (class "Default")
      (node (ref "C81") (pin "1") (pinfunction "1_1") (pintype "passive"))
      (node (ref "S1") (pin "11") (pinfunction "11_11") (pintype "bidirectional"))
    )
    (net (code "21") (name "Net-(C82-Pad1)") (class "Default")
      (node (ref "C82") (pin "1") (pinfunction "1_1") (pintype "passive"))
      (node (ref "S1") (pin "12") (pinfunction "12_12") (pintype "bidirectional"))
    )
    (net (code "22") (name "Net-(C83-Pad1)") (class "Default")
      (node (ref "C83") (pin "1") (pinfunction "1_1") (pintype "passive"))
      (node (ref "S2") (pin "4") (pinfunction "4_4") (pintype "bidirectional"))
    )
    (net (code "23") (name "Net-(C84-Pad1)") (class "Default")
      (node (ref "C84") (pin "1") (pinfunction "1_1") (pintype "passive"))
      (node (ref "S2") (pin "5") (pinfunction "5_5") (pintype "bidirectional"))
    )
    (net (code "24") (name "Net-(C85-Pad1)") (class "Default")
      (node (ref "C85") (pin "1") (pinfunction "1_1") (pintype "passive"))
      (node (ref "S2") (pin "6") (pinfunction "6_6") (pintype "bidirectional"))
    )
    (net (code "25") (name "Net-(C86-Pad1)") (class "Default")
      (node (ref "C86") (pin "1") (pinfunction "1_1") (pintype "passive"))
      (node (ref "S2") (pin "7") (pinfunction "7_7") (pintype "bidirectional"))
    )
    (net (code "26") (name "Net-(C87-Pad1)") (class "Default")
      (node (ref "C87") (pin "1") (pinfunction "1_1") (pintype "passive"))
      (node (ref "S2") (pin "8") (pinfunction "8_8") (pintype "bidirectional"))
    )
    (net (code "27") (name "Net-(C88-Pad1)") (class "Default")
      (node (ref "C88") (pin "1") (pinfunction "1_1") (pintype "passive"))
      (node (ref "S2") (pin "9") (pinfunction "9_9") (pintype "bidirectional"))
    )
    (net (code "28") (name "Net-(C89-Pad1)") (class "Default")
      (node (ref "C89") (pin "1") (pinfunction "1_1") (pintype "passive"))
      (node (ref "S2") (pin "10") (pinfunction "10_10") (pintype "bidirectional"))
    )
    (net (code "29") (name "Net-(C90-Pad1)") (class "Default")
      (node (ref "C90") (pin "1") (pinfunction "1_1") (pintype "passive"))
      (node (ref "S2") (pin "11") (pinfunction "11_11") (pintype "bidirectional"))
    )
    (net (code "30") (name "Net-(C91-Pad1)") (class "Default")
      (node (ref "C91") (pin "1") (pinfunction "1_1") (pintype "passive"))
      (node (ref "S2") (pin "12") (pinfunction "12_12") (pintype "bidirectional"))
    )
    (net (code "31") (name "Net-(D1-PadA)") (class "Default")
      (node (ref "D1") (pin "A") (pinfunction "A_A") (pintype "passive"))
      (node (ref "R2") (pin "1") (pinfunction "1_1") (pintype "passive"))
      (node (ref "R3") (pin "2") (pinfunction "2_2") (pintype "passive"))
    )
    (net (code "32") (name "Net-(D1-PadC)") (class "Default")
      (node (ref "D1") (pin "C") (pinfunction "C_C") (pintype "passive"))
      (node (ref "D4") (pin "A") (pinfunction "A_A") (pintype "passive"))
      (node (ref "R2") (pin "2") (pinfunction "2_2") (pintype "passive"))
      (node (ref "S3") (pin "2") (pinfunction "2_2") (pintype "passive"))
    )
    (net (code "33") (name "Net-(D2-A)") (class "Default")
      (node (ref "C1") (pin "2") (pinfunction "2_2") (pintype "passive"))
      (node (ref "D2") (pin "2") (pinfunction "A_2") (pintype "passive"))
      (node (ref "R53") (pin "E") (pinfunction "3_E") (pintype "passive"))
      (node (ref "R7") (pin "2") (pinfunction "2_2") (pintype "passive"))
      (node (ref "R9") (pin "E") (pinfunction "3_E") (pintype "passive"))
    )
    (net (code "34") (name "Net-(D4-PadC)") (class "Default")
      (node (ref "D4") (pin "C") (pinfunction "C_C") (pintype "passive"))
      (node (ref "R60") (pin "2") (pinfunction "2_2") (pintype "passive"))
    )
    (net (code "35") (name "Net-(D9-PadA)") (class "Default")
      (node (ref "D9") (pin "A") (pinfunction "A_A") (pintype "passive"))
      (node (ref "R66") (pin "1") (pinfunction "1_1") (pintype "passive"))
    )
    (net (code "36") (name "Net-(D12-1)") (class "Default")
      (node (ref "D12") (pin "A") (pinfunction "1_A") (pintype "passive"))
      (node (ref "R58") (pin "1") (pinfunction "1_1") (pintype "passive"))
      (node (ref "X4") (pin "2") (pinfunction "2_2") (pintype "passive"))
      (node (ref "X4") (pin "3") (pinfunction "2_3") (pintype "passive"))
      (node (ref "X4") (pin "4") (pinfunction "2_4") (pintype "passive"))
      (node (ref "X4") (pin "5") (pinfunction "2_5") (pintype "passive"))
    )
    (net (code "37") (name "Net-(D12-2)") (class "Default")
      (node (ref "C6") (pin "2") (pinfunction "2_2") (pintype "passive"))
      (node (ref "D12") (pin "C") (pinfunction "2_C") (pintype "passive"))
      (node (ref "R65") (pin "1") (pinfunction "1_1") (pintype "passive"))
      (node (ref "X4") (pin "1") (pinfunction "1_1") (pintype "passive"))
    )
    (net (code "38") (name "Net-(D13-1)") (class "Default")
      (node (ref "D13") (pin "A") (pinfunction "1_A") (pintype "passive"))
      (node (ref "R6") (pin "1") (pinfunction "1_1") (pintype "passive"))
      (node (ref "X2") (pin "2") (pinfunction "2_2") (pintype "passive"))
      (node (ref "X2") (pin "3") (pinfunction "2_3") (pintype "passive"))
      (node (ref "X2") (pin "4") (pinfunction "2_4") (pintype "passive"))
      (node (ref "X2") (pin "5") (pinfunction "2_5") (pintype "passive"))
    )
    (net (code "39") (name "Net-(D13-2)") (class "Default")
      (node (ref "C5") (pin "2") (pinfunction "2_2") (pintype "passive"))
      (node (ref "D13") (pin "C") (pinfunction "2_C") (pintype "passive"))
      (node (ref "R64") (pin "1") (pinfunction "1_1") (pintype "passive"))
      (node (ref "X2") (pin "1") (pinfunction "1_1") (pintype "passive"))
    )
    (net (code "40") (name "Net-(D14-PadA)") (class "Default")
      (node (ref "D14") (pin "A") (pinfunction "A_A") (pintype "passive"))
      (node (ref "R18") (pin "1") (pinfunction "1_1") (pintype "passive"))
    )
    (net (code "41") (name "Net-(IC1-IN+)") (class "Default")
      (node (ref "IC1") (pin "3") (pinfunction "IN+_3") (pintype "input"))
      (node (ref "R20") (pin "1") (pinfunction "1_1") (pintype "passive"))
      (node (ref "R24") (pin "2") (pinfunction "2_2") (pintype "passive"))
    )
    (net (code "42") (name "Net-(IC1-IN-)") (class "Default")
      (node (ref "IC1") (pin "2") (pinfunction "IN-_2") (pintype "input"))
      (node (ref "R19") (pin "1") (pinfunction "1_1") (pintype "passive"))
      (node (ref "R23") (pin "2") (pinfunction "2_2") (pintype "passive"))
    )
    (net (code "43") (name "Net-(IC1-OUT)") (class "Default")
      (node (ref "IC1") (pin "6") (pinfunction "OUT_6") (pintype "output"))
      (node (ref "R23") (pin "1") (pinfunction "1_1") (pintype "passive"))
      (node (ref "R25") (pin "2") (pinfunction "2_2") (pintype "passive"))
      (node (ref "R40") (pin "2") (pinfunction "2_2") (pintype "passive"))
    )
    (net (code "44") (name "Net-(IC2-COMP)") (class "Default")
      (node (ref "C13") (pin "1") (pinfunction "1_1") (pintype "passive"))
      (node (ref "IC2") (pin "8") (pinfunction "COMP_8") (pintype "passive"))
    )
    (net (code "45") (name "Net-(IC2-IN+)") (class "Default")
      (node (ref "C10") (pin "1") (pinfunction "1_1") (pintype "passive"))
      (node (ref "IC2") (pin "3") (pinfunction "IN+_3") (pintype "input"))
      (node (ref "JP4") (pin "2") (pinfunction "2_2") (pintype "passive"))
      (node (ref "R14") (pin "2") (pinfunction "2_2") (pintype "passive"))
      (node (ref "R16") (pin "2") (pinfunction "2_2") (pintype "passive"))
      (node (ref "R70") (pin "2") (pinfunction "SA_2") (pintype "passive"))
      (node (ref "X6") (pin "2") (pinfunction "S_2") (pintype "passive"))
    )
    (net (code "46") (name "Net-(IC2-IN-)") (class "Default")
      (node (ref "C14") (pin "1") (pinfunction "1_1") (pintype "passive"))
      (node (ref "IC2") (pin "2") (pinfunction "IN-_2") (pintype "input"))
      (node (ref "R13") (pin "2") (pinfunction "2_2") (pintype "passive"))
      (node (ref "R21") (pin "2") (pinfunction "2_2") (pintype "passive"))
    )
    (net (code "47") (name "Net-(IC2-OUT)") (class "Default")
      (node (ref "C13") (pin "2") (pinfunction "2_2") (pintype "passive"))
      (node (ref "C14") (pin "2") (pinfunction "2_2") (pintype "passive"))
      (node (ref "IC2") (pin "6") (pinfunction "OUT_6") (pintype "output"))
      (node (ref "R19") (pin "2") (pinfunction "2_2") (pintype "passive"))
      (node (ref "R21") (pin "1") (pinfunction "1_1") (pintype "passive"))
    )
    (net (code "48") (name "Net-(IC3-IN)") (class "Default")
      (node (ref "IC3") (pin "3") (pinfunction "IN_3") (pintype "input"))
      (node (ref "R57") (pin "1") (pinfunction "1_1") (pintype "passive"))
    )
    (net (code "49") (name "Net-(IC3-OUT)") (class "Default")
      (node (ref "IC3") (pin "6") (pinfunction "OUT_6") (pintype "output"))
      (node (ref "R63") (pin "2") (pinfunction "2_2") (pintype "passive"))
    )
    (net (code "50") (name "Net-(IC4-COMP)") (class "Default")
      (node (ref "C12") (pin "1") (pinfunction "1_1") (pintype "passive"))
      (node (ref "IC4") (pin "8") (pinfunction "COMP_8") (pintype "passive"))
    )
    (net (code "51") (name "Net-(IC4-IN+)") (class "Default")
      (node (ref "C11") (pin "1") (pinfunction "1_1") (pintype "passive"))
      (node (ref "IC4") (pin "3") (pinfunction "IN+_3") (pintype "input"))
      (node (ref "JP3") (pin "1") (pinfunction "1_1") (pintype "passive"))
      (node (ref "R15") (pin "1") (pinfunction "1_1") (pintype "passive"))
      (node (ref "R17") (pin "2") (pinfunction "2_2") (pintype "passive"))
      (node (ref "R70") (pin "3") (pinfunction "SB_3") (pintype "passive"))
      (node (ref "X6") (pin "3") (pinfunction "S_3") (pintype "passive"))
    )
    (net (code "52") (name "Net-(IC4-IN-)") (class "Default")
      (node (ref "C15") (pin "1") (pinfunction "1_1") (pintype "passive"))
      (node (ref "IC4") (pin "2") (pinfunction "IN-_2") (pintype "input"))
      (node (ref "R13") (pin "1") (pinfunction "1_1") (pintype "passive"))
      (node (ref "R22") (pin "2") (pinfunction "2_2") (pintype "passive"))
    )
    (net (code "53") (name "Net-(IC4-OUT)") (class "Default")
      (node (ref "C12") (pin "2") (pinfunction "2_2") (pintype "passive"))
      (node (ref "C15") (pin "2") (pinfunction "2_2") (pintype "passive"))
      (node (ref "IC4") (pin "6") (pinfunction "OUT_6") (pintype "output"))
      (node (ref "R20") (pin "2") (pinfunction "2_2") (pintype "passive"))
      (node (ref "R22") (pin "1") (pinfunction "1_1") (pintype "passive"))
    )
    (net (code "54") (name "Net-(IC5-IN+)") (class "Default")
      (node (ref "IC5") (pin "3") (pinfunction "IN+_3") (pintype "input"))
      (node (ref "R42") (pin "1") (pinfunction "1_1") (pintype "passive"))
    )
    (net (code "55") (name "Net-(IC5-IN-)") (class "Default")
      (node (ref "IC5") (pin "2") (pinfunction "IN-_2") (pintype "input"))
      (node (ref "R43") (pin "2") (pinfunction "2_2") (pintype "passive"))
    )
    (net (code "56") (name "Net-(IC5-OUT)") (class "Default")
      (node (ref "C72") (pin "2") (pinfunction "2_2") (pintype "passive"))
      (node (ref "C73") (pin "2") (pinfunction "2_2") (pintype "passive"))
      (node (ref "C74") (pin "2") (pinfunction "2_2") (pintype "passive"))
      (node (ref "C75") (pin "2") (pinfunction "2_2") (pintype "passive"))
      (node (ref "C76") (pin "2") (pinfunction "2_2") (pintype "passive"))
      (node (ref "C77") (pin "2") (pinfunction "2_2") (pintype "passive"))
      (node (ref "C78") (pin "2") (pinfunction "2_2") (pintype "passive"))
      (node (ref "C79") (pin "2") (pinfunction "2_2") (pintype "passive"))
      (node (ref "C80") (pin "2") (pinfunction "2_2") (pintype "passive"))
      (node (ref "C81") (pin "2") (pinfunction "2_2") (pintype "passive"))
      (node (ref "C82") (pin "2") (pinfunction "2_2") (pintype "passive"))
      (node (ref "IC5") (pin "6") (pinfunction "OUT_6") (pintype "output"))
      (node (ref "R45") (pin "2") (pinfunction "2_2") (pintype "passive"))
      (node (ref "S1") (pin "1") (pinfunction "1_1") (pintype "bidirectional"))
    )
    (net (code "57") (name "Net-(IC6-IN+)") (class "Default")
      (node (ref "IC6") (pin "3") (pinfunction "IN+_3") (pintype "input"))
      (node (ref "R25") (pin "1") (pinfunction "1_1") (pintype "passive"))
    )
    (net (code "58") (name "Net-(IC6-OUT)") (class "Default")
      (node (ref "IC6") (pin "6") (pinfunction "OUT_6") (pintype "output"))
      (node (ref "R27") (pin "2") (pinfunction "2_2") (pintype "passive"))
    )
    (net (code "59") (name "Net-(IC7-COMP)") (class "Default")
      (node (ref "C19") (pin "1") (pinfunction "1_1") (pintype "passive"))
      (node (ref "IC7") (pin "8") (pinfunction "COMP_8") (pintype "passive"))
    )
    (net (code "60") (name "Net-(IC7-IN+)") (class "Default")
      (node (ref "C16") (pin "1") (pinfunction "1_1") (pintype "passive"))
      (node (ref "IC7") (pin "3") (pinfunction "IN+_3") (pintype "input"))
      (node (ref "R29") (pin "2") (pinfunction "2_2") (pintype "passive"))
      (node (ref "R31") (pin "2") (pinfunction "2_2") (pintype "passive"))
    )
    (net (code "61") (name "Net-(IC7-IN-)") (class "Default")
      (node (ref "C20") (pin "1") (pinfunction "1_1") (pintype "passive"))
      (node (ref "IC7") (pin "2") (pinfunction "IN-_2") (pintype "input"))
      (node (ref "R28") (pin "2") (pinfunction "2_2") (pintype "passive"))
      (node (ref "R36") (pin "2") (pinfunction "2_2") (pintype "passive"))
    )
    (net (code "62") (name "Net-(IC7-OUT)") (class "Default")
      (node (ref "C19") (pin "2") (pinfunction "2_2") (pintype "passive"))
      (node (ref "C20") (pin "2") (pinfunction "2_2") (pintype "passive"))
      (node (ref "IC7") (pin "6") (pinfunction "OUT_6") (pintype "output"))
      (node (ref "R34") (pin "2") (pinfunction "2_2") (pintype "passive"))
      (node (ref "R36") (pin "1") (pinfunction "1_1") (pintype "passive"))
    )
    (net (code "63") (name "Net-(IC8-COMP)") (class "Default")
      (node (ref "C18") (pin "1") (pinfunction "1_1") (pintype "passive"))
      (node (ref "IC8") (pin "8") (pinfunction "COMP_8") (pintype "passive"))
    )
    (net (code "64") (name "Net-(IC8-IN+)") (class "Default")
      (node (ref "C17") (pin "1") (pinfunction "1_1") (pintype "passive"))
      (node (ref "IC8") (pin "3") (pinfunction "IN+_3") (pintype "input"))
      (node (ref "R30") (pin "1") (pinfunction "1_1") (pintype "passive"))
      (node (ref "R32") (pin "2") (pinfunction "2_2") (pintype "passive"))
    )
    (net (code "65") (name "Net-(IC8-IN-)") (class "Default")
      (node (ref "C21") (pin "1") (pinfunction "1_1") (pintype "passive"))
      (node (ref "IC8") (pin "2") (pinfunction "IN-_2") (pintype "input"))
      (node (ref "R28") (pin "1") (pinfunction "1_1") (pintype "passive"))
      (node (ref "R37") (pin "2") (pinfunction "2_2") (pintype "passive"))
    )
    (net (code "66") (name "Net-(IC8-OUT)") (class "Default")
      (node (ref "C18") (pin "2") (pinfunction "2_2") (pintype "passive"))
      (node (ref "C21") (pin "2") (pinfunction "2_2") (pintype "passive"))
      (node (ref "IC8") (pin "6") (pinfunction "OUT_6") (pintype "output"))
      (node (ref "R35") (pin "2") (pinfunction "2_2") (pintype "passive"))
      (node (ref "R37") (pin "1") (pinfunction "1_1") (pintype "passive"))
    )
    (net (code "67") (name "Net-(IC9-IN+)") (class "Default")
      (node (ref "IC9") (pin "3") (pinfunction "IN+_3") (pintype "input"))
      (node (ref "R35") (pin "1") (pinfunction "1_1") (pintype "passive"))
      (node (ref "R39") (pin "2") (pinfunction "2_2") (pintype "passive"))
    )
    (net (code "68") (name "Net-(IC9-IN-)") (class "Default")
      (node (ref "IC9") (pin "2") (pinfunction "IN-_2") (pintype "input"))
      (node (ref "R34") (pin "1") (pinfunction "1_1") (pintype "passive"))
      (node (ref "R38") (pin "2") (pinfunction "2_2") (pintype "passive"))
    )
    (net (code "69") (name "Net-(IC9-OUT)") (class "Default")
      (node (ref "IC9") (pin "6") (pinfunction "OUT_6") (pintype "output"))
      (node (ref "R33") (pin "2") (pinfunction "2_2") (pintype "passive"))
      (node (ref "R38") (pin "1") (pinfunction "1_1") (pintype "passive"))
      (node (ref "TP1") (pin "P$1") (pinfunction "P$1_P$1") (pintype "bidirectional"))
    )
    (net (code "70") (name "Net-(IC10-IN-)") (class "Default")
      (node (ref "IC10") (pin "2") (pinfunction "IN-_2") (pintype "input"))
      (node (ref "R33") (pin "1") (pinfunction "1_1") (pintype "passive"))
      (node (ref "R40") (pin "1") (pinfunction "1_1") (pintype "passive"))
      (node (ref "R41") (pin "2") (pinfunction "2_2") (pintype "passive"))
    )
    (net (code "71") (name "Net-(IC10-OUT)") (class "Default")
      (node (ref "IC10") (pin "6") (pinfunction "OUT_6") (pintype "output"))
      (node (ref "R0") (pin "2") (pinfunction "2_2") (pintype "passive"))
      (node (ref "R0") (pin "3") (pinfunction "3_3") (pintype "passive"))
      (node (ref "R42") (pin "2") (pinfunction "2_2") (pintype "passive"))
    )
    (net (code "72") (name "Net-(IC11-IN+)") (class "Default")
      (node (ref "IC11") (pin "3") (pinfunction "IN+_3") (pintype "input"))
      (node (ref "R45") (pin "1") (pinfunction "1_1") (pintype "passive"))
      (node (ref "R46") (pin "1") (pinfunction "1_1") (pintype "passive"))
    )
    (net (code "73") (name "Net-(IC11-IN-)") (class "Default")
      (node (ref "IC11") (pin "2") (pinfunction "IN-_2") (pintype "input"))
      (node (ref "R47") (pin "2") (pinfunction "2_2") (pintype "passive"))
    )
    (net (code "74") (name "Net-(IC11-OUT)") (class "Default")
      (node (ref "IC11") (pin "6") (pinfunction "OUT_6") (pintype "output"))
      (node (ref "R48") (pin "1") (pinfunction "1_1") (pintype "passive"))
      (node (ref "R50") (pin "A") (pinfunction "1_A") (pintype "passive"))
      (node (ref "R50") (pin "S") (pinfunction "2_S") (pintype "passive"))
    )
    (net (code "75") (name "Net-(IC12-IN+)") (class "Default")
      (node (ref "C23") (pin "1") (pinfunction "1_1") (pintype "passive"))
      (node (ref "IC12") (pin "3") (pinfunction "IN+_3") (pintype "input"))
      (node (ref "R52") (pin "1") (pinfunction "1_1") (pintype "passive"))
    )
    (net (code "76") (name "Net-(IC12-IN-)") (class "Default")
      (node (ref "IC12") (pin "2") (pinfunction "IN-_2") (pintype "input"))
      (node (ref "IC12") (pin "6") (pinfunction "OUT_6") (pintype "output"))
      (node (ref "S3") (pin "1") (pinfunction "1_1") (pintype "passive"))
    )
    (net (code "77") (name "Net-(IC13-IN+)") (class "Default")
      (node (ref "IC13") (pin "3") (pinfunction "IN+_3") (pintype "input"))
      (node (ref "R4") (pin "1") (pinfunction "1_1") (pintype "passive"))
      (node (ref "R5") (pin "1") (pinfunction "1_1") (pintype "passive"))
      (node (ref "R6") (pin "2") (pinfunction "2_2") (pintype "passive"))
    )
    (net (code "78") (name "Net-(IC13-IN-)") (class "Default")
      (node (ref "IC13") (pin "2") (pinfunction "IN-_2") (pintype "input"))
      (node (ref "R3") (pin "1") (pinfunction "1_1") (pintype "passive"))
      (node (ref "R55") (pin "1") (pinfunction "1_1") (pintype "passive"))
      (node (ref "R8") (pin "2") (pinfunction "2_2") (pintype "passive"))
    )
    (net (code "79") (name "Net-(IC13-OUT)") (class "Default")
      (node (ref "IC13") (pin "6") (pinfunction "OUT_6") (pintype "output"))
      (node (ref "R61") (pin "2") (pinfunction "2_2") (pintype "passive"))
      (node (ref "R8") (pin "1") (pinfunction "1_1") (pintype "passive"))
    )
    (net (code "80") (name "Net-(IC14-IN+)") (class "Default")
      (node (ref "C2") (pin "2") (pinfunction "2_2") (pintype "passive"))
      (node (ref "IC14") (pin "3") (pinfunction "IN+_3") (pintype "input"))
      (node (ref "R9") (pin "S") (pinfunction "2_S") (pintype "passive"))
    )
    (net (code "81") (name "Net-(IC15-IN+)") (class "Default")
      (node (ref "C4") (pin "2") (pinfunction "2_2") (pintype "passive"))
      (node (ref "IC15") (pin "3") (pinfunction "IN+_3") (pintype "input"))
      (node (ref "R53") (pin "S") (pinfunction "2_S") (pintype "passive"))
    )
    (net (code "82") (name "Net-(IC16-IN+)") (class "Default")
      (node (ref "IC16") (pin "3") (pinfunction "IN+_3") (pintype "input"))
      (node (ref "R58") (pin "2") (pinfunction "2_2") (pintype "passive"))
      (node (ref "R60") (pin "1") (pinfunction "1_1") (pintype "passive"))
    )
    (net (code "83") (name "Net-(IC16-IN-)") (class "Default")
      (node (ref "IC16") (pin "2") (pinfunction "IN-_2") (pintype "input"))
      (node (ref "R56") (pin "1") (pinfunction "1_1") (pintype "passive"))
      (node (ref "R59") (pin "2") (pinfunction "2_2") (pintype "passive"))
    )
    (net (code "84") (name "Net-(IC16-OUT)") (class "Default")
      (node (ref "IC16") (pin "6") (pinfunction "OUT_6") (pintype "output"))
      (node (ref "R57") (pin "2") (pinfunction "2_2") (pintype "passive"))
      (node (ref "R59") (pin "1") (pinfunction "1_1") (pintype "passive"))
    )
    (net (code "85") (name "Net-(IC17-IN)") (class "Default")
      (node (ref "IC17") (pin "3") (pinfunction "IN_3") (pintype "input"))
      (node (ref "R61") (pin "1") (pinfunction "1_1") (pintype "passive"))
    )
    (net (code "86") (name "Net-(IC17-OUT)") (class "Default")
      (node (ref "IC17") (pin "6") (pinfunction "OUT_6") (pintype "output"))
      (node (ref "R62") (pin "2") (pinfunction "2_2") (pintype "passive"))
    )
    (net (code "87") (name "Net-(JP1-Pad1)") (class "Default")
      (node (ref "JP1") (pin "1") (pinfunction "1_1") (pintype "passive"))
      (node (ref "R10") (pin "1") (pinfunction "1_1") (pintype "passive"))
      (node (ref "R55") (pin "2") (pinfunction "2_2") (pintype "passive"))
    )
    (net (code "88") (name "Net-(JP2-Pad1)") (class "Default")
      (node (ref "JP2") (pin "1") (pinfunction "1_1") (pintype "passive"))
      (node (ref "R54") (pin "1") (pinfunction "1_1") (pintype "passive"))
      (node (ref "R56") (pin "2") (pinfunction "2_2") (pintype "passive"))
    )
    (net (code "89") (name "Net-(Q1-G)") (class "Default")
      (node (ref "Q1") (pin "1") (pinfunction "G_1") (pintype "passive"))
      (node (ref "Q3") (pin "1") (pinfunction "G_1") (pintype "passive"))
      (node (ref "Q5") (pin "1") (pinfunction "G_1") (pintype "passive"))
      (node (ref "R11") (pin "1") (pinfunction "1_1") (pintype "passive"))
      (node (ref "T1") (pin "3") (pinfunction "C_3") (pintype "passive"))
      (node (ref "X8") (pin "1") (pinfunction "S_1") (pintype "passive"))
    )
    (net (code "90") (name "Net-(Q1-S)") (class "Default")
      (node (ref "Q1") (pin "3") (pinfunction "S_3") (pintype "passive"))
      (node (ref "Q3") (pin "3") (pinfunction "S_3") (pintype "passive"))
      (node (ref "Q5") (pin "3") (pinfunction "S_3") (pintype "passive"))
      (node (ref "R26") (pin "2") (pinfunction "2_2") (pintype "passive"))
      (node (ref "T1") (pin "1") (pinfunction "B_1") (pintype "passive"))
      (node (ref "X8") (pin "2") (pinfunction "S_2") (pintype "passive"))
    )
    (net (code "91") (name "Net-(R0-Pad1)") (class "Default")
      (node (ref "R0") (pin "1") (pinfunction "1_1") (pintype "passive"))
      (node (ref "R41") (pin "1") (pinfunction "1_1") (pintype "passive"))
    )
    (net (code "92") (name "Net-(R1-1)") (class "Default")
      (node (ref "R1") (pin "A") (pinfunction "1_A") (pintype "passive"))
      (node (ref "R1") (pin "S") (pinfunction "2_S") (pintype "passive"))
      (node (ref "R44") (pin "1") (pinfunction "1_1") (pintype "passive"))
    )
    (net (code "93") (name "Net-(R27-Pad1)") (class "Default")
      (node (ref "R27") (pin "1") (pinfunction "1_1") (pintype "passive"))
      (node (ref "X1") (pin "1") (pinfunction "1_1") (pintype "passive"))
    )
    (net (code "94") (name "Net-(R29-Pad1)") (class "Default")
      (node (ref "R29") (pin "1") (pinfunction "1_1") (pintype "passive"))
      (node (ref "X3") (pin "1") (pinfunction "1_1") (pintype "passive"))
    )
    (net (code "95") (name "Net-(R30-Pad2)") (class "Default")
      (node (ref "R30") (pin "2") (pinfunction "2_2") (pintype "passive"))
      (node (ref "X3") (pin "2") (pinfunction "2_2") (pintype "passive"))
    )
    (net (code "96") (name "Net-(R43-Pad1)") (class "Default")
      (node (ref "R43") (pin "1") (pinfunction "1_1") (pintype "passive"))
      (node (ref "R44") (pin "2") (pinfunction "2_2") (pintype "passive"))
      (node (ref "S1") (pin "13") (pinfunction "13_13") (pintype "bidirectional"))
    )
    (net (code "97") (name "Net-(R47-Pad1)") (class "Default")
      (node (ref "R47") (pin "1") (pinfunction "1_1") (pintype "passive"))
      (node (ref "R48") (pin "2") (pinfunction "2_2") (pintype "passive"))
      (node (ref "R49") (pin "2") (pinfunction "2_2") (pintype "passive"))
    )
    (net (code "98") (name "Net-(R50-3)") (class "Default")
      (node (ref "R50") (pin "E") (pinfunction "3_E") (pintype "passive"))
      (node (ref "R52") (pin "2") (pinfunction "2_2") (pintype "passive"))
    )
    (net (code "99") (name "Net-(R51-1)") (class "Default")
      (node (ref "R49") (pin "1") (pinfunction "1_1") (pintype "passive"))
      (node (ref "R51") (pin "A") (pinfunction "1_A") (pintype "passive"))
      (node (ref "R51") (pin "S") (pinfunction "2_S") (pintype "passive"))
    )
    (net (code "100") (name "Net-(R51-3)") (class "Default")
      (node (ref "R51") (pin "E") (pinfunction "3_E") (pintype "passive"))
      (node (ref "S2") (pin "13") (pinfunction "13_13") (pintype "bidirectional"))
    )
    (net (code "101") (name "Net-(R70-A)") (class "Default")
      (node (ref "R14") (pin "1") (pinfunction "1_1") (pintype "passive"))
      (node (ref "R70") (pin "1") (pinfunction "A_1") (pintype "passive"))
    )
    (net (code "102") (name "Net-(R70-B)") (class "Default")
      (node (ref "R15") (pin "2") (pinfunction "2_2") (pintype "passive"))
      (node (ref "R70") (pin "4") (pinfunction "B_4") (pintype "passive"))
    )
    (net (code "103") (name "unconnected-(IC2-OFF-Pad1)") (class "Default")
      (node (ref "IC2") (pin "1") (pinfunction "OFF_1") (pintype "passive"))
    )
    (net (code "104") (name "unconnected-(IC2-OFF-Pad5)") (class "Default")
      (node (ref "IC2") (pin "5") (pinfunction "OFF_5") (pintype "passive"))
    )
    (net (code "105") (name "unconnected-(IC3-BW-Pad1)") (class "Default")
      (node (ref "IC3") (pin "1") (pinfunction "BW_1") (pintype "passive"))
    )
    (net (code "106") (name "unconnected-(IC4-OFF-Pad1)") (class "Default")
      (node (ref "IC4") (pin "1") (pinfunction "OFF_1") (pintype "passive"))
    )
    (net (code "107") (name "unconnected-(IC4-OFF-Pad5)") (class "Default")
      (node (ref "IC4") (pin "5") (pinfunction "OFF_5") (pintype "passive"))
    )
    (net (code "108") (name "unconnected-(IC7-OFF-Pad1)") (class "Default")
      (node (ref "IC7") (pin "1") (pinfunction "OFF_1") (pintype "passive"))
    )
    (net (code "109") (name "unconnected-(IC7-OFF-Pad5)") (class "Default")
      (node (ref "IC7") (pin "5") (pinfunction "OFF_5") (pintype "passive"))
    )
    (net (code "110") (name "unconnected-(IC8-OFF-Pad1)") (class "Default")
      (node (ref "IC8") (pin "1") (pinfunction "OFF_1") (pintype "passive"))
    )
    (net (code "111") (name "unconnected-(IC8-OFF-Pad5)") (class "Default")
      (node (ref "IC8") (pin "5") (pinfunction "OFF_5") (pintype "passive"))
    )
    (net (code "112") (name "unconnected-(IC17-BW-Pad1)") (class "Default")
      (node (ref "IC17") (pin "1") (pinfunction "BW_1") (pintype "passive"))
    )
    (net (code "113") (name "unconnected-(Q1-D-Pad4)") (class "Default")
      (node (ref "Q1") (pin "4") (pinfunction "D_4") (pintype "passive"))
    )
    (net (code "114") (name "unconnected-(Q3-D-Pad4)") (class "Default")
      (node (ref "Q3") (pin "4") (pinfunction "D_4") (pintype "passive"))
    )
    (net (code "115") (name "unconnected-(Q5-D-Pad2)") (class "Default")
      (node (ref "Q5") (pin "2") (pinfunction "D_2") (pintype "passive"))
    )
    (net (code "116") (name "unconnected-(R11-Pad2)") (class "Default")
      (node (ref "R11") (pin "2") (pinfunction "2_2") (pintype "passive"))
    )
  )
)
